# mayfly_platform_revC.net
KiCad netlist of a schematic drawn in EAGLE
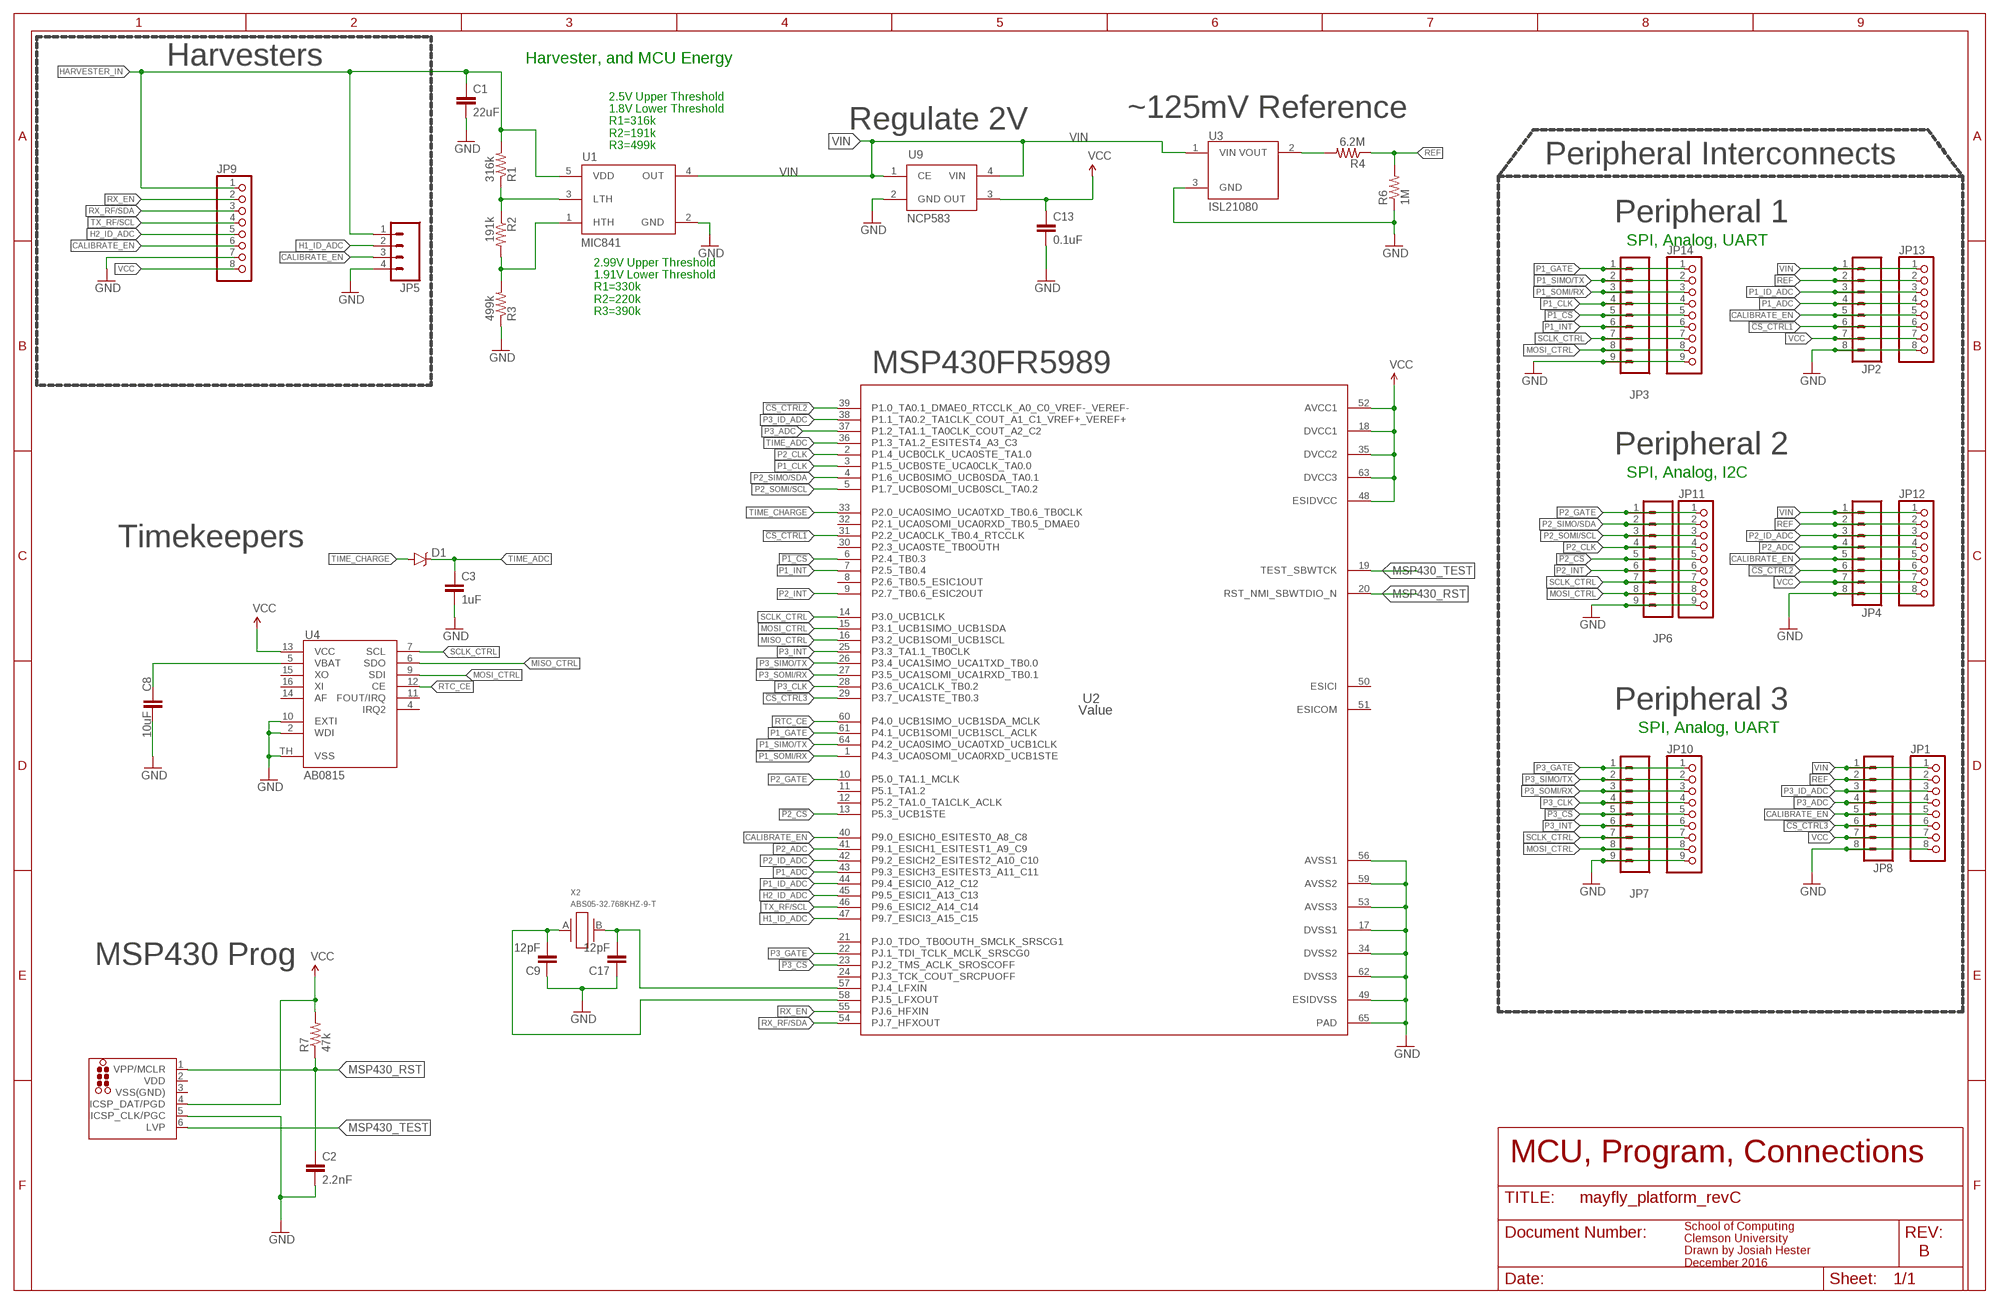
[diagram p0: schematic, sheet 1]

(export (version "E")
  (design (tool "Eeschema 10.0.6"))
  (components
    (comp (ref "C1")
      (value "22uF")
      (footprint "eagle-import:1210")
      (fields (field (name "MANUFACTURERPARTNUMBER") "  CL32A226KAJNNNE"))
      (libsource (lib "eagle-import") (part "CAP1210"))
    )
    (comp (ref "C2")
      (value "2.2nF")
      (footprint "eagle-import:0603")
      (fields (field (name "MPN") "  06035C222KAT2A"))
      (libsource (lib "eagle-import") (part "C-EU0603"))
    )
    (comp (ref "C3")
      (value "1uF")
      (footprint "eagle-import:0603")
      (fields (field (name "MANUFACTURERPARTNUMBER") "  0603YD105KAT2A"))
      (libsource (lib "eagle-import") (part "C-EU0603"))
    )
    (comp (ref "C8")
      (value "10uF")
      (footprint "eagle-import:0805")
      (fields (field (name "MPN") "0805YD106KAT2A"))
      (libsource (lib "eagle-import") (part "CAP0805"))
    )
    (comp (ref "C9")
      (value "12pF")
      (footprint "eagle-import:0603")
      (fields (field (name "MPN") "CL10C120JB8NNNC"))
      (libsource (lib "eagle-import") (part "C-EU0603"))
    )
    (comp (ref "C13")
      (value "0.1uF")
      (footprint "eagle-import:0603")
      (fields (field (name "MANUFACTURERPARTNUMBER") "  0603YC104KAT2A"))
      (libsource (lib "eagle-import") (part "C-EU0603"))
    )
    (comp (ref "C17")
      (value "12pF")
      (footprint "eagle-import:0603")
      (fields (field (name "MPN") "CL10C120JB8NNNC"))
      (libsource (lib "eagle-import") (part "C-EU0603"))
    )
    (comp (ref "D1")
      (value "RB751")
      (footprint "eagle-import:SOD-523")
      (fields (field (name "MPN") "BAS40-02V-V-G-08 "))
      (libsource (lib "eagle-import") (part "DIODE-SCHOTTKY-RB751"))
    )
    (comp (ref "J1")
      (value "TC2030-MCP-NL")
      (footprint "eagle-import:TC2030-MCP-NL")
      (libsource (lib "eagle-import") (part "TC2030-MCP-NL"))
    )
    (comp (ref "JP1")
      (value "PINHD-1X8")
      (footprint "eagle-import:1X08")
      (libsource (lib "eagle-import") (part "PINHD-1X8"))
    )
    (comp (ref "JP2")
      (value "M081.27MM")
      (footprint "eagle-import:1X08-1.27MM")
      (fields (field (name "MPN") "851-43-008-10-001000 "))
      (libsource (lib "eagle-import") (part "M081.27MM"))
    )
    (comp (ref "JP3")
      (value "M091.27MM")
      (footprint "eagle-import:1X09-1.27MM")
      (fields (field (name "MPN") "851-87-009-10-001101 "))
      (libsource (lib "eagle-import") (part "M091.27MM"))
    )
    (comp (ref "JP4")
      (value "M081.27MM")
      (footprint "eagle-import:1X08-1.27MM")
      (fields (field (name "MPN") "851-43-008-10-001000 "))
      (libsource (lib "eagle-import") (part "M081.27MM"))
    )
    (comp (ref "JP5")
      (value "M041.27MM")
      (footprint "eagle-import:1X04-1.27MM")
      (fields (field (name "MANUFACTURERPARTNUMBER") "851-43-004-10-001000 "))
      (libsource (lib "eagle-import") (part "M041.27MM"))
    )
    (comp (ref "JP6")
      (value "M091.27MM")
      (footprint "eagle-import:1X09-1.27MM")
      (fields (field (name "MPN") "851-87-009-10-001101 "))
      (libsource (lib "eagle-import") (part "M091.27MM"))
    )
    (comp (ref "JP7")
      (value "M091.27MM")
      (footprint "eagle-import:1X09-1.27MM")
      (fields (field (name "MPN") "851-87-009-10-001101 "))
      (libsource (lib "eagle-import") (part "M091.27MM"))
    )
    (comp (ref "JP8")
      (value "M081.27MM")
      (footprint "eagle-import:1X08-1.27MM")
      (fields (field (name "MPN") "851-43-008-10-001000 "))
      (libsource (lib "eagle-import") (part "M081.27MM"))
    )
    (comp (ref "JP9")
      (value "PINHD-1X8")
      (footprint "eagle-import:1X08")
      (libsource (lib "eagle-import") (part "PINHD-1X8"))
    )
    (comp (ref "JP10")
      (value "PINHD-1X9")
      (footprint "eagle-import:1X09")
      (libsource (lib "eagle-import") (part "PINHD-1X9"))
    )
    (comp (ref "JP11")
      (value "PINHD-1X9")
      (footprint "eagle-import:1X09")
      (libsource (lib "eagle-import") (part "PINHD-1X9"))
    )
    (comp (ref "JP12")
      (value "PINHD-1X8")
      (footprint "eagle-import:1X08")
      (libsource (lib "eagle-import") (part "PINHD-1X8"))
    )
    (comp (ref "JP13")
      (value "PINHD-1X8")
      (footprint "eagle-import:1X08")
      (libsource (lib "eagle-import") (part "PINHD-1X8"))
    )
    (comp (ref "JP14")
      (value "PINHD-1X9")
      (footprint "eagle-import:1X09")
      (libsource (lib "eagle-import") (part "PINHD-1X9"))
    )
    (comp (ref "R1")
      (value "316k")
      (footprint "eagle-import:0603")
      (fields (field (name "MANUFACTURERPARTNUMBER") "RC0603FR-07316KL "))
      (libsource (lib "eagle-import") (part "R-EU0603"))
    )
    (comp (ref "R2")
      (value "191k")
      (footprint "eagle-import:0603")
      (fields (field (name "MANUFACTURERPARTNUMBER") "RC0603FR-07191KL "))
      (libsource (lib "eagle-import") (part "R-EU0603"))
    )
    (comp (ref "R3")
      (value "499k")
      (footprint "eagle-import:0603")
      (fields (field (name "MANUFACTURERPARTNUMBER") "RC0603FR-07499KL"))
      (libsource (lib "eagle-import") (part "R-EU0603"))
    )
    (comp (ref "R4")
      (value "6.2M")
      (footprint "eagle-import:0603")
      (fields (field (name "MPN") "CRCW06036M20FKEA"))
      (libsource (lib "eagle-import") (part "R-EU0603"))
    )
    (comp (ref "R6")
      (value "1M")
      (footprint "eagle-import:0603")
      (fields (field (name "MPN") "RC0603FR-071ML"))
      (libsource (lib "eagle-import") (part "R-EU0603"))
    )
    (comp (ref "R7")
      (value "47k")
      (footprint "eagle-import:0603")
      (fields (field (name "MPN") "  CRCW060347K0JNEA"))
      (libsource (lib "eagle-import") (part "R-EU0603"))
    )
    (comp (ref "U1")
      (value "MIC841")
      (footprint "eagle-import:SC70-5")
      (fields (field (name "MPN") "MIC841HYC5-TR"))
      (libsource (lib "eagle-import") (part "MIC841"))
    )
    (comp (ref "U2")
      (value "Value")
      (footprint "eagle-import:RGC0064B")
      (fields
        (field (name "ALTERNATEPARTNUMBER") "MSP430FR5989IRGCT")
        (field (name "MANUFACTURER") "Texas Instruments")
        (field (name "PARTNUMBER") "MSP430FR5989IRGCR")
      )
      (libsource (lib "eagle-import") (part "MSP430FR5989IRGCR"))
    )
    (comp (ref "U3")
      (value "ISL21080")
      (footprint "eagle-import:SOT-23")
      (fields (field (name "MPN") "ISL21080DIH309Z-TK"))
      (libsource (lib "eagle-import") (part "ISL21080"))
    )
    (comp (ref "U4")
      (value "AB0815")
      (footprint "eagle-import:QFN16")
      (fields (field (name "MPN") "AB0815-T3"))
      (libsource (lib "eagle-import") (part "AB0815"))
    )
    (comp (ref "U9")
      (value "NCP583")
      (footprint "eagle-import:SC82-AB_1PRIMARY")
      (fields (field (name "MPN") "NCP583SQ18T1G"))
      (libsource (lib "eagle-import") (part "NCP583"))
    )
    (comp (ref "X2")
      (value "ABS05-32.768KHZ-9-T")
      (footprint "eagle-import:ABS05")
      (fields (field (name "MPN") "ABS05-32.768KHZ-9-T "))
      (libsource (lib "eagle-import") (part "ABS05-32.768KHZ-9-T"))
    )
  )
  (nets
    (net (code "1") (name "/VDD") (class "Default")
      (node (ref "J1") (pin "2") (pinfunction "VDD_2") (pintype "power_in"))
    )
    (net (code "2") (name "/VSS(GND)") (class "Default")
      (node (ref "J1") (pin "3") (pinfunction "VSS(GND)_3") (pintype "power_in"))
    )
    (net (code "3") (name "/~{CS_CTRL1}") (class "Default")
      (node (ref "JP13") (pin "6") (pinfunction "6_6") (pintype "passive"))
      (node (ref "JP2") (pin "6") (pinfunction "6_6") (pintype "passive"))
      (node (ref "U2") (pin "31") (pinfunction "P2.2_UCA0CLK_TB0.4_RTCCLK_31") (pintype "bidirectional"))
    )
    (net (code "4") (name "/~{CS_CTRL2}") (class "Default")
      (node (ref "JP12") (pin "6") (pinfunction "6_6") (pintype "passive"))
      (node (ref "JP4") (pin "6") (pinfunction "6_6") (pintype "passive"))
      (node (ref "U2") (pin "39") (pinfunction "P1.0_TA0.1_DMAE0_RTCCLK_A0_C0_VREF-_VEREF-_39") (pintype "bidirectional"))
    )
    (net (code "5") (name "/~{CS_CTRL3}") (class "Default")
      (node (ref "JP1") (pin "6") (pinfunction "6_6") (pintype "passive"))
      (node (ref "JP8") (pin "6") (pinfunction "6_6") (pintype "passive"))
      (node (ref "U2") (pin "29") (pinfunction "P3.7_UCA1STE_TB0.3_29") (pintype "bidirectional"))
    )
    (net (code "6") (name "/~{P1_CS}") (class "Default")
      (node (ref "JP14") (pin "5") (pinfunction "5_5") (pintype "passive"))
      (node (ref "JP3") (pin "5") (pinfunction "5_5") (pintype "passive"))
      (node (ref "U2") (pin "6") (pinfunction "P2.4_TB0.3_6") (pintype "bidirectional"))
    )
    (net (code "7") (name "/~{P2_CS}") (class "Default")
      (node (ref "JP11") (pin "5") (pinfunction "5_5") (pintype "passive"))
      (node (ref "JP6") (pin "5") (pinfunction "5_5") (pintype "passive"))
      (node (ref "U2") (pin "13") (pinfunction "P5.3_UCB1STE_13") (pintype "bidirectional"))
    )
    (net (code "8") (name "/~{P3_CS}") (class "Default")
      (node (ref "JP10") (pin "5") (pinfunction "5_5") (pintype "passive"))
      (node (ref "JP7") (pin "5") (pinfunction "5_5") (pintype "passive"))
      (node (ref "U2") (pin "23") (pinfunction "PJ.2_TMS_ACLK_SROSCOFF_23") (pintype "bidirectional"))
    )
    (net (code "9") (name "CALIBRATE_EN") (class "Default")
      (node (ref "JP1") (pin "5") (pinfunction "5_5") (pintype "passive"))
      (node (ref "JP12") (pin "5") (pinfunction "5_5") (pintype "passive"))
      (node (ref "JP13") (pin "5") (pinfunction "5_5") (pintype "passive"))
      (node (ref "JP2") (pin "5") (pinfunction "5_5") (pintype "passive"))
      (node (ref "JP4") (pin "5") (pinfunction "5_5") (pintype "passive"))
      (node (ref "JP5") (pin "3") (pinfunction "3_3") (pintype "passive"))
      (node (ref "JP8") (pin "5") (pinfunction "5_5") (pintype "passive"))
      (node (ref "JP9") (pin "6") (pinfunction "6_6") (pintype "passive"))
      (node (ref "U2") (pin "40") (pinfunction "P9.0_ESICH0_ESITEST0_A8_C8_40") (pintype "bidirectional"))
    )
    (net (code "10") (name "GND") (class "Default")
      (node (ref "C1") (pin "2") (pinfunction "2_2") (pintype "passive"))
      (node (ref "C13") (pin "2") (pinfunction "2_2") (pintype "passive"))
      (node (ref "C17") (pin "1") (pinfunction "1_1") (pintype "passive"))
      (node (ref "C2") (pin "2") (pinfunction "2_2") (pintype "passive"))
      (node (ref "C3") (pin "2") (pinfunction "2_2") (pintype "passive"))
      (node (ref "C8") (pin "2") (pinfunction "2_2") (pintype "passive"))
      (node (ref "C9") (pin "1") (pinfunction "1_1") (pintype "passive"))
      (node (ref "J1") (pin "5") (pinfunction "ICSP_CLK/PGC_5") (pintype "output"))
      (node (ref "JP1") (pin "8") (pinfunction "8_8") (pintype "passive"))
      (node (ref "JP10") (pin "9") (pinfunction "9_9") (pintype "passive"))
      (node (ref "JP11") (pin "9") (pinfunction "9_9") (pintype "passive"))
      (node (ref "JP12") (pin "8") (pinfunction "8_8") (pintype "passive"))
      (node (ref "JP13") (pin "8") (pinfunction "8_8") (pintype "passive"))
      (node (ref "JP14") (pin "9") (pinfunction "9_9") (pintype "passive"))
      (node (ref "JP2") (pin "8") (pinfunction "8_8") (pintype "passive"))
      (node (ref "JP3") (pin "9") (pinfunction "9_9") (pintype "passive"))
      (node (ref "JP4") (pin "8") (pinfunction "8_8") (pintype "passive"))
      (node (ref "JP5") (pin "4") (pinfunction "4_4") (pintype "passive"))
      (node (ref "JP6") (pin "9") (pinfunction "9_9") (pintype "passive"))
      (node (ref "JP7") (pin "9") (pinfunction "9_9") (pintype "passive"))
      (node (ref "JP8") (pin "8") (pinfunction "8_8") (pintype "passive"))
      (node (ref "JP9") (pin "7") (pinfunction "7_7") (pintype "passive"))
      (node (ref "R3") (pin "1") (pinfunction "1_1") (pintype "passive"))
      (node (ref "R6") (pin "1") (pinfunction "1_1") (pintype "passive"))
      (node (ref "U1") (pin "2") (pinfunction "GND_2") (pintype "bidirectional"))
      (node (ref "U2") (pin "17") (pinfunction "DVSS1_17") (pintype "power_in"))
      (node (ref "U2") (pin "34") (pinfunction "DVSS2_34") (pintype "power_in"))
      (node (ref "U2") (pin "49") (pinfunction "ESIDVSS_49") (pintype "power_in"))
      (node (ref "U2") (pin "53") (pinfunction "AVSS3_53") (pintype "power_in"))
      (node (ref "U2") (pin "56") (pinfunction "AVSS1_56") (pintype "power_in"))
      (node (ref "U2") (pin "59") (pinfunction "AVSS2_59") (pintype "power_in"))
      (node (ref "U2") (pin "62") (pinfunction "DVSS3_62") (pintype "power_in"))
      (node (ref "U2") (pin "65") (pinfunction "PAD_65") (pintype "power_in"))
      (node (ref "U3") (pin "3") (pinfunction "GND_3") (pintype "bidirectional"))
      (node (ref "U4") (pin "10") (pinfunction "EXTI_10") (pintype "bidirectional"))
      (node (ref "U4") (pin "2") (pinfunction "WDI_2") (pintype "bidirectional"))
      (node (ref "U4") (pin "TH") (pinfunction "VSS_TH") (pintype "bidirectional"))
      (node (ref "U9") (pin "2") (pinfunction "GND_2") (pintype "bidirectional"))
    )
    (net (code "11") (name "H1_ID_ADC") (class "Default")
      (node (ref "JP5") (pin "2") (pinfunction "2_2") (pintype "passive"))
      (node (ref "U2") (pin "47") (pinfunction "P9.7_ESICI3_A15_C15_47") (pintype "bidirectional"))
    )
    (net (code "12") (name "H2_ID_ADC") (class "Default")
      (node (ref "JP9") (pin "5") (pinfunction "5_5") (pintype "passive"))
      (node (ref "U2") (pin "45") (pinfunction "P9.5_ESICI1_A13_C13_45") (pintype "bidirectional"))
    )
    (net (code "13") (name "HARVESTER_IN") (class "Default")
      (node (ref "C1") (pin "1") (pinfunction "1_1") (pintype "passive"))
      (node (ref "JP5") (pin "1") (pinfunction "1_1") (pintype "passive"))
      (node (ref "JP9") (pin "1") (pinfunction "1_1") (pintype "passive"))
      (node (ref "R1") (pin "2") (pinfunction "2_2") (pintype "passive"))
      (node (ref "U1") (pin "5") (pinfunction "VDD_5") (pintype "bidirectional"))
    )
    (net (code "14") (name "MISO_CTRL") (class "Default")
      (node (ref "U2") (pin "16") (pinfunction "P3.2_UCB1SOMI_UCB1SCL_16") (pintype "bidirectional"))
      (node (ref "U4") (pin "6") (pinfunction "SDO_6") (pintype "bidirectional"))
    )
    (net (code "15") (name "MOSI_CTRL") (class "Default")
      (node (ref "JP10") (pin "8") (pinfunction "8_8") (pintype "passive"))
      (node (ref "JP11") (pin "8") (pinfunction "8_8") (pintype "passive"))
      (node (ref "JP14") (pin "8") (pinfunction "8_8") (pintype "passive"))
      (node (ref "JP3") (pin "8") (pinfunction "8_8") (pintype "passive"))
      (node (ref "JP6") (pin "8") (pinfunction "8_8") (pintype "passive"))
      (node (ref "JP7") (pin "8") (pinfunction "8_8") (pintype "passive"))
      (node (ref "U2") (pin "15") (pinfunction "P3.1_UCB1SIMO_UCB1SDA_15") (pintype "bidirectional"))
      (node (ref "U4") (pin "9") (pinfunction "SDI_9") (pintype "bidirectional"))
    )
    (net (code "16") (name "MSP430_RST") (class "Default")
      (node (ref "C2") (pin "1") (pinfunction "1_1") (pintype "passive"))
      (node (ref "J1") (pin "1") (pinfunction "VPP/MCLR_1") (pintype "passive"))
      (node (ref "R7") (pin "1") (pinfunction "1_1") (pintype "passive"))
      (node (ref "U2") (pin "20") (pinfunction "RST_NMI_SBWTDIO_N_20") (pintype "bidirectional"))
    )
    (net (code "17") (name "MSP430_TEST") (class "Default")
      (node (ref "J1") (pin "6") (pinfunction "LVP_6") (pintype "bidirectional"))
      (node (ref "U2") (pin "19") (pinfunction "TEST_SBWTCK_19") (pintype "input"))
    )
    (net (code "18") (name "Net-(U1-HTH)") (class "Default")
      (node (ref "R2") (pin "2") (pinfunction "2_2") (pintype "passive"))
      (node (ref "R3") (pin "2") (pinfunction "2_2") (pintype "passive"))
      (node (ref "U1") (pin "1") (pinfunction "HTH_1") (pintype "bidirectional"))
    )
    (net (code "19") (name "Net-(U1-LTH)") (class "Default")
      (node (ref "R1") (pin "1") (pinfunction "1_1") (pintype "passive"))
      (node (ref "R2") (pin "1") (pinfunction "1_1") (pintype "passive"))
      (node (ref "U1") (pin "3") (pinfunction "LTH_3") (pintype "bidirectional"))
    )
    (net (code "20") (name "Net-(U2-PJ.4_LFXIN)") (class "Default")
      (node (ref "C17") (pin "2") (pinfunction "2_2") (pintype "passive"))
      (node (ref "U2") (pin "57") (pinfunction "PJ.4_LFXIN_57") (pintype "bidirectional"))
      (node (ref "X2") (pin "B") (pinfunction "2_B") (pintype "bidirectional"))
    )
    (net (code "21") (name "Net-(U2-PJ.5_LFXOUT)") (class "Default")
      (node (ref "C9") (pin "2") (pinfunction "2_2") (pintype "passive"))
      (node (ref "U2") (pin "58") (pinfunction "PJ.5_LFXOUT_58") (pintype "bidirectional"))
      (node (ref "X2") (pin "A") (pinfunction "1_A") (pintype "bidirectional"))
    )
    (net (code "22") (name "Net-(U3-VOUT)") (class "Default")
      (node (ref "R4") (pin "2") (pinfunction "2_2") (pintype "passive"))
      (node (ref "U3") (pin "2") (pinfunction "VOUT_2") (pintype "bidirectional"))
    )
    (net (code "23") (name "Net-(U4-VBAT)") (class "Default")
      (node (ref "C8") (pin "1") (pinfunction "1_1") (pintype "passive"))
      (node (ref "U4") (pin "5") (pinfunction "VBAT_5") (pintype "bidirectional"))
    )
    (net (code "24") (name "P1_ADC") (class "Default")
      (node (ref "JP13") (pin "4") (pinfunction "4_4") (pintype "passive"))
      (node (ref "JP2") (pin "4") (pinfunction "4_4") (pintype "passive"))
      (node (ref "U2") (pin "43") (pinfunction "P9.3_ESICH3_ESITEST3_A11_C11_43") (pintype "bidirectional"))
    )
    (net (code "25") (name "P1_CLK") (class "Default")
      (node (ref "JP14") (pin "4") (pinfunction "4_4") (pintype "passive"))
      (node (ref "JP3") (pin "4") (pinfunction "4_4") (pintype "passive"))
      (node (ref "U2") (pin "3") (pinfunction "P1.5_UCB0STE_UCA0CLK_TA0.0_3") (pintype "bidirectional"))
    )
    (net (code "26") (name "P1_GATE") (class "Default")
      (node (ref "JP14") (pin "1") (pinfunction "1_1") (pintype "passive"))
      (node (ref "JP3") (pin "1") (pinfunction "1_1") (pintype "passive"))
      (node (ref "U2") (pin "61") (pinfunction "P4.1_UCB1SOMI_UCB1SCL_ACLK_61") (pintype "bidirectional"))
    )
    (net (code "27") (name "P1_ID_ADC") (class "Default")
      (node (ref "JP13") (pin "3") (pinfunction "3_3") (pintype "passive"))
      (node (ref "JP2") (pin "3") (pinfunction "3_3") (pintype "passive"))
      (node (ref "U2") (pin "44") (pinfunction "P9.4_ESICI0_A12_C12_44") (pintype "bidirectional"))
    )
    (net (code "28") (name "P1_INT") (class "Default")
      (node (ref "JP14") (pin "6") (pinfunction "6_6") (pintype "passive"))
      (node (ref "JP3") (pin "6") (pinfunction "6_6") (pintype "passive"))
      (node (ref "U2") (pin "7") (pinfunction "P2.5_TB0.4_7") (pintype "bidirectional"))
    )
    (net (code "29") (name "P1_SIMO{slash}TX") (class "Default")
      (node (ref "JP14") (pin "2") (pinfunction "2_2") (pintype "passive"))
      (node (ref "JP3") (pin "2") (pinfunction "2_2") (pintype "passive"))
      (node (ref "U2") (pin "64") (pinfunction "P4.2_UCA0SIMO_UCA0TXD_UCB1CLK_64") (pintype "bidirectional"))
    )
    (net (code "30") (name "P1_SOMI{slash}RX") (class "Default")
      (node (ref "JP14") (pin "3") (pinfunction "3_3") (pintype "passive"))
      (node (ref "JP3") (pin "3") (pinfunction "3_3") (pintype "passive"))
      (node (ref "U2") (pin "1") (pinfunction "P4.3_UCA0SOMI_UCA0RXD_UCB1STE_1") (pintype "bidirectional"))
    )
    (net (code "31") (name "P2_ADC") (class "Default")
      (node (ref "JP12") (pin "4") (pinfunction "4_4") (pintype "passive"))
      (node (ref "JP4") (pin "4") (pinfunction "4_4") (pintype "passive"))
      (node (ref "U2") (pin "41") (pinfunction "P9.1_ESICH1_ESITEST1_A9_C9_41") (pintype "bidirectional"))
    )
    (net (code "32") (name "P2_CLK") (class "Default")
      (node (ref "JP11") (pin "4") (pinfunction "4_4") (pintype "passive"))
      (node (ref "JP6") (pin "4") (pinfunction "4_4") (pintype "passive"))
      (node (ref "U2") (pin "2") (pinfunction "P1.4_UCB0CLK_UCA0STE_TA1.0_2") (pintype "bidirectional"))
    )
    (net (code "33") (name "P2_GATE") (class "Default")
      (node (ref "JP11") (pin "1") (pinfunction "1_1") (pintype "passive"))
      (node (ref "JP6") (pin "1") (pinfunction "1_1") (pintype "passive"))
      (node (ref "U2") (pin "10") (pinfunction "P5.0_TA1.1_MCLK_10") (pintype "bidirectional"))
    )
    (net (code "34") (name "P2_ID_ADC") (class "Default")
      (node (ref "JP12") (pin "3") (pinfunction "3_3") (pintype "passive"))
      (node (ref "JP4") (pin "3") (pinfunction "3_3") (pintype "passive"))
      (node (ref "U2") (pin "42") (pinfunction "P9.2_ESICH2_ESITEST2_A10_C10_42") (pintype "bidirectional"))
    )
    (net (code "35") (name "P2_INT") (class "Default")
      (node (ref "JP11") (pin "6") (pinfunction "6_6") (pintype "passive"))
      (node (ref "JP6") (pin "6") (pinfunction "6_6") (pintype "passive"))
      (node (ref "U2") (pin "9") (pinfunction "P2.7_TB0.6_ESIC2OUT_9") (pintype "bidirectional"))
    )
    (net (code "36") (name "P2_SIMO{slash}SDA") (class "Default")
      (node (ref "JP11") (pin "2") (pinfunction "2_2") (pintype "passive"))
      (node (ref "JP6") (pin "2") (pinfunction "2_2") (pintype "passive"))
      (node (ref "U2") (pin "4") (pinfunction "P1.6_UCB0SIMO_UCB0SDA_TA0.1_4") (pintype "bidirectional"))
    )
    (net (code "37") (name "P2_SOMI{slash}SCL") (class "Default")
      (node (ref "JP11") (pin "3") (pinfunction "3_3") (pintype "passive"))
      (node (ref "JP6") (pin "3") (pinfunction "3_3") (pintype "passive"))
      (node (ref "U2") (pin "5") (pinfunction "P1.7_UCB0SOMI_UCB0SCL_TA0.2_5") (pintype "bidirectional"))
    )
    (net (code "38") (name "P3_ADC") (class "Default")
      (node (ref "JP1") (pin "4") (pinfunction "4_4") (pintype "passive"))
      (node (ref "JP8") (pin "4") (pinfunction "4_4") (pintype "passive"))
      (node (ref "U2") (pin "37") (pinfunction "P1.2_TA1.1_TA0CLK_COUT_A2_C2_37") (pintype "bidirectional"))
    )
    (net (code "39") (name "P3_CLK") (class "Default")
      (node (ref "JP10") (pin "4") (pinfunction "4_4") (pintype "passive"))
      (node (ref "JP7") (pin "4") (pinfunction "4_4") (pintype "passive"))
      (node (ref "U2") (pin "28") (pinfunction "P3.6_UCA1CLK_TB0.2_28") (pintype "bidirectional"))
    )
    (net (code "40") (name "P3_GATE") (class "Default")
      (node (ref "JP10") (pin "1") (pinfunction "1_1") (pintype "passive"))
      (node (ref "JP7") (pin "1") (pinfunction "1_1") (pintype "passive"))
      (node (ref "U2") (pin "22") (pinfunction "PJ.1_TDI_TCLK_MCLK_SRSCG0_22") (pintype "bidirectional"))
    )
    (net (code "41") (name "P3_ID_ADC") (class "Default")
      (node (ref "JP1") (pin "3") (pinfunction "3_3") (pintype "passive"))
      (node (ref "JP8") (pin "3") (pinfunction "3_3") (pintype "passive"))
      (node (ref "U2") (pin "38") (pinfunction "P1.1_TA0.2_TA1CLK_COUT_A1_C1_VREF+_VEREF+_38") (pintype "bidirectional"))
    )
    (net (code "42") (name "P3_INT") (class "Default")
      (node (ref "JP10") (pin "6") (pinfunction "6_6") (pintype "passive"))
      (node (ref "JP7") (pin "6") (pinfunction "6_6") (pintype "passive"))
      (node (ref "U2") (pin "25") (pinfunction "P3.3_TA1.1_TB0CLK_25") (pintype "bidirectional"))
    )
    (net (code "43") (name "P3_SIMO{slash}TX") (class "Default")
      (node (ref "JP10") (pin "2") (pinfunction "2_2") (pintype "passive"))
      (node (ref "JP7") (pin "2") (pinfunction "2_2") (pintype "passive"))
      (node (ref "U2") (pin "26") (pinfunction "P3.4_UCA1SIMO_UCA1TXD_TB0.0_26") (pintype "bidirectional"))
    )
    (net (code "44") (name "P3_SOMI{slash}RX") (class "Default")
      (node (ref "JP10") (pin "3") (pinfunction "3_3") (pintype "passive"))
      (node (ref "JP7") (pin "3") (pinfunction "3_3") (pintype "passive"))
      (node (ref "U2") (pin "27") (pinfunction "P3.5_UCA1SOMI_UCA1RXD_TB0.1_27") (pintype "bidirectional"))
    )
    (net (code "45") (name "REF") (class "Default")
      (node (ref "JP1") (pin "2") (pinfunction "2_2") (pintype "passive"))
      (node (ref "JP12") (pin "2") (pinfunction "2_2") (pintype "passive"))
      (node (ref "JP13") (pin "2") (pinfunction "2_2") (pintype "passive"))
      (node (ref "JP2") (pin "2") (pinfunction "2_2") (pintype "passive"))
      (node (ref "JP4") (pin "2") (pinfunction "2_2") (pintype "passive"))
      (node (ref "JP8") (pin "2") (pinfunction "2_2") (pintype "passive"))
      (node (ref "R4") (pin "1") (pinfunction "1_1") (pintype "passive"))
      (node (ref "R6") (pin "2") (pinfunction "2_2") (pintype "passive"))
    )
    (net (code "46") (name "RTC_CE") (class "Default")
      (node (ref "U2") (pin "60") (pinfunction "P4.0_UCB1SIMO_UCB1SDA_MCLK_60") (pintype "bidirectional"))
      (node (ref "U4") (pin "12") (pinfunction "CE_12") (pintype "bidirectional"))
    )
    (net (code "47") (name "RX_EN") (class "Default")
      (node (ref "JP9") (pin "2") (pinfunction "2_2") (pintype "passive"))
      (node (ref "U2") (pin "55") (pinfunction "PJ.6_HFXIN_55") (pintype "bidirectional"))
    )
    (net (code "48") (name "RX_RF{slash}SDA") (class "Default")
      (node (ref "JP9") (pin "3") (pinfunction "3_3") (pintype "passive"))
      (node (ref "U2") (pin "54") (pinfunction "PJ.7_HFXOUT_54") (pintype "bidirectional"))
    )
    (net (code "49") (name "SCLK_CTRL") (class "Default")
      (node (ref "JP10") (pin "7") (pinfunction "7_7") (pintype "passive"))
      (node (ref "JP11") (pin "7") (pinfunction "7_7") (pintype "passive"))
      (node (ref "JP14") (pin "7") (pinfunction "7_7") (pintype "passive"))
      (node (ref "JP3") (pin "7") (pinfunction "7_7") (pintype "passive"))
      (node (ref "JP6") (pin "7") (pinfunction "7_7") (pintype "passive"))
      (node (ref "JP7") (pin "7") (pinfunction "7_7") (pintype "passive"))
      (node (ref "U2") (pin "14") (pinfunction "P3.0_UCB1CLK_14") (pintype "bidirectional"))
      (node (ref "U4") (pin "7") (pinfunction "SCL_7") (pintype "bidirectional"))
    )
    (net (code "50") (name "TIME_ADC") (class "Default")
      (node (ref "C3") (pin "1") (pinfunction "1_1") (pintype "passive"))
      (node (ref "D1") (pin "C") (pinfunction "C_C") (pintype "passive"))
      (node (ref "U2") (pin "36") (pinfunction "P1.3_TA1.2_ESITEST4_A3_C3_36") (pintype "bidirectional"))
    )
    (net (code "51") (name "TIME_CHARGE") (class "Default")
      (node (ref "D1") (pin "A") (pinfunction "A_A") (pintype "passive"))
      (node (ref "U2") (pin "33") (pinfunction "P2.0_UCA0SIMO_UCA0TXD_TB0.6_TB0CLK_33") (pintype "bidirectional"))
    )
    (net (code "52") (name "TX_RF{slash}SCL") (class "Default")
      (node (ref "JP9") (pin "4") (pinfunction "4_4") (pintype "passive"))
      (node (ref "U2") (pin "46") (pinfunction "P9.6_ESICI2_A14_C14_46") (pintype "bidirectional"))
    )
    (net (code "53") (name "VCC") (class "Default")
      (node (ref "C13") (pin "1") (pinfunction "1_1") (pintype "passive"))
      (node (ref "J1") (pin "4") (pinfunction "ICSP_DAT/PGD_4") (pintype "bidirectional"))
      (node (ref "JP1") (pin "7") (pinfunction "7_7") (pintype "passive"))
      (node (ref "JP12") (pin "7") (pinfunction "7_7") (pintype "passive"))
      (node (ref "JP13") (pin "7") (pinfunction "7_7") (pintype "passive"))
      (node (ref "JP2") (pin "7") (pinfunction "7_7") (pintype "passive"))
      (node (ref "JP4") (pin "7") (pinfunction "7_7") (pintype "passive"))
      (node (ref "JP8") (pin "7") (pinfunction "7_7") (pintype "passive"))
      (node (ref "JP9") (pin "8") (pinfunction "8_8") (pintype "passive"))
      (node (ref "R7") (pin "2") (pinfunction "2_2") (pintype "passive"))
      (node (ref "U2") (pin "18") (pinfunction "DVCC1_18") (pintype "power_in"))
      (node (ref "U2") (pin "35") (pinfunction "DVCC2_35") (pintype "power_in"))
      (node (ref "U2") (pin "48") (pinfunction "ESIDVCC_48") (pintype "power_in"))
      (node (ref "U2") (pin "52") (pinfunction "AVCC1_52") (pintype "power_in"))
      (node (ref "U2") (pin "63") (pinfunction "DVCC3_63") (pintype "power_in"))
      (node (ref "U4") (pin "13") (pinfunction "VCC_13") (pintype "bidirectional"))
      (node (ref "U9") (pin "3") (pinfunction "OUT_3") (pintype "bidirectional"))
    )
    (net (code "54") (name "VIN") (class "Default")
      (node (ref "JP1") (pin "1") (pinfunction "1_1") (pintype "passive"))
      (node (ref "JP12") (pin "1") (pinfunction "1_1") (pintype "passive"))
      (node (ref "JP13") (pin "1") (pinfunction "1_1") (pintype "passive"))
      (node (ref "JP2") (pin "1") (pinfunction "1_1") (pintype "passive"))
      (node (ref "JP4") (pin "1") (pinfunction "1_1") (pintype "passive"))
      (node (ref "JP8") (pin "1") (pinfunction "1_1") (pintype "passive"))
      (node (ref "U1") (pin "4") (pinfunction "OUT_4") (pintype "bidirectional"))
      (node (ref "U3") (pin "1") (pinfunction "VIN_1") (pintype "bidirectional"))
      (node (ref "U9") (pin "1") (pinfunction "CE_1") (pintype "bidirectional"))
      (node (ref "U9") (pin "4") (pinfunction "VIN_4") (pintype "bidirectional"))
    )
    (net (code "55") (name "unconnected-(U2-ESICI-Pad50)") (class "Default")
      (node (ref "U2") (pin "50") (pinfunction "ESICI_50") (pintype "input"))
    )
    (net (code "56") (name "unconnected-(U2-ESICOM-Pad51)") (class "Default")
      (node (ref "U2") (pin "51") (pinfunction "ESICOM_51") (pintype "passive"))
    )
    (net (code "57") (name "unconnected-(U2-P2.1_UCA0SOMI_UCA0RXD_TB0.5_DMAE0-Pad32)") (class "Default")
      (node (ref "U2") (pin "32") (pinfunction "P2.1_UCA0SOMI_UCA0RXD_TB0.5_DMAE0_32") (pintype "bidirectional"))
    )
    (net (code "58") (name "unconnected-(U2-P2.3_UCA0STE_TB0OUTH-Pad30)") (class "Default")
      (node (ref "U2") (pin "30") (pinfunction "P2.3_UCA0STE_TB0OUTH_30") (pintype "bidirectional"))
    )
    (net (code "59") (name "unconnected-(U2-P2.6_TB0.5_ESIC1OUT-Pad8)") (class "Default")
      (node (ref "U2") (pin "8") (pinfunction "P2.6_TB0.5_ESIC1OUT_8") (pintype "bidirectional"))
    )
    (net (code "60") (name "unconnected-(U2-P5.1_TA1.2-Pad11)") (class "Default")
      (node (ref "U2") (pin "11") (pinfunction "P5.1_TA1.2_11") (pintype "bidirectional"))
    )
    (net (code "61") (name "unconnected-(U2-P5.2_TA1.0_TA1CLK_ACLK-Pad12)") (class "Default")
      (node (ref "U2") (pin "12") (pinfunction "P5.2_TA1.0_TA1CLK_ACLK_12") (pintype "bidirectional"))
    )
    (net (code "62") (name "unconnected-(U2-PJ.0_TDO_TB0OUTH_SMCLK_SRSCG1-Pad21)") (class "Default")
      (node (ref "U2") (pin "21") (pinfunction "PJ.0_TDO_TB0OUTH_SMCLK_SRSCG1_21") (pintype "bidirectional"))
    )
    (net (code "63") (name "unconnected-(U2-PJ.3_TCK_COUT_SRCPUOFF-Pad24)") (class "Default")
      (node (ref "U2") (pin "24") (pinfunction "PJ.3_TCK_COUT_SRCPUOFF_24") (pintype "bidirectional"))
    )
    (net (code "64") (name "unconnected-(U4-AF-Pad14)") (class "Default")
      (node (ref "U4") (pin "14") (pinfunction "AF_14") (pintype "bidirectional"))
    )
    (net (code "65") (name "unconnected-(U4-FOUT{slash}IRQ-Pad11)") (class "Default")
      (node (ref "U4") (pin "11") (pinfunction "FOUT/IRQ_11") (pintype "bidirectional"))
    )
    (net (code "66") (name "unconnected-(U4-IRQ2-Pad4)") (class "Default")
      (node (ref "U4") (pin "4") (pinfunction "IRQ2_4") (pintype "bidirectional"))
    )
    (net (code "67") (name "unconnected-(U4-XI-Pad16)") (class "Default")
      (node (ref "U4") (pin "16") (pinfunction "XI_16") (pintype "bidirectional"))
    )
    (net (code "68") (name "unconnected-(U4-XO-Pad15)") (class "Default")
      (node (ref "U4") (pin "15") (pinfunction "XO_15") (pintype "bidirectional"))
    )
  )
)
